# 24V_Power_Supply.net
KiCad netlist of a schematic drawn in Altium Designer
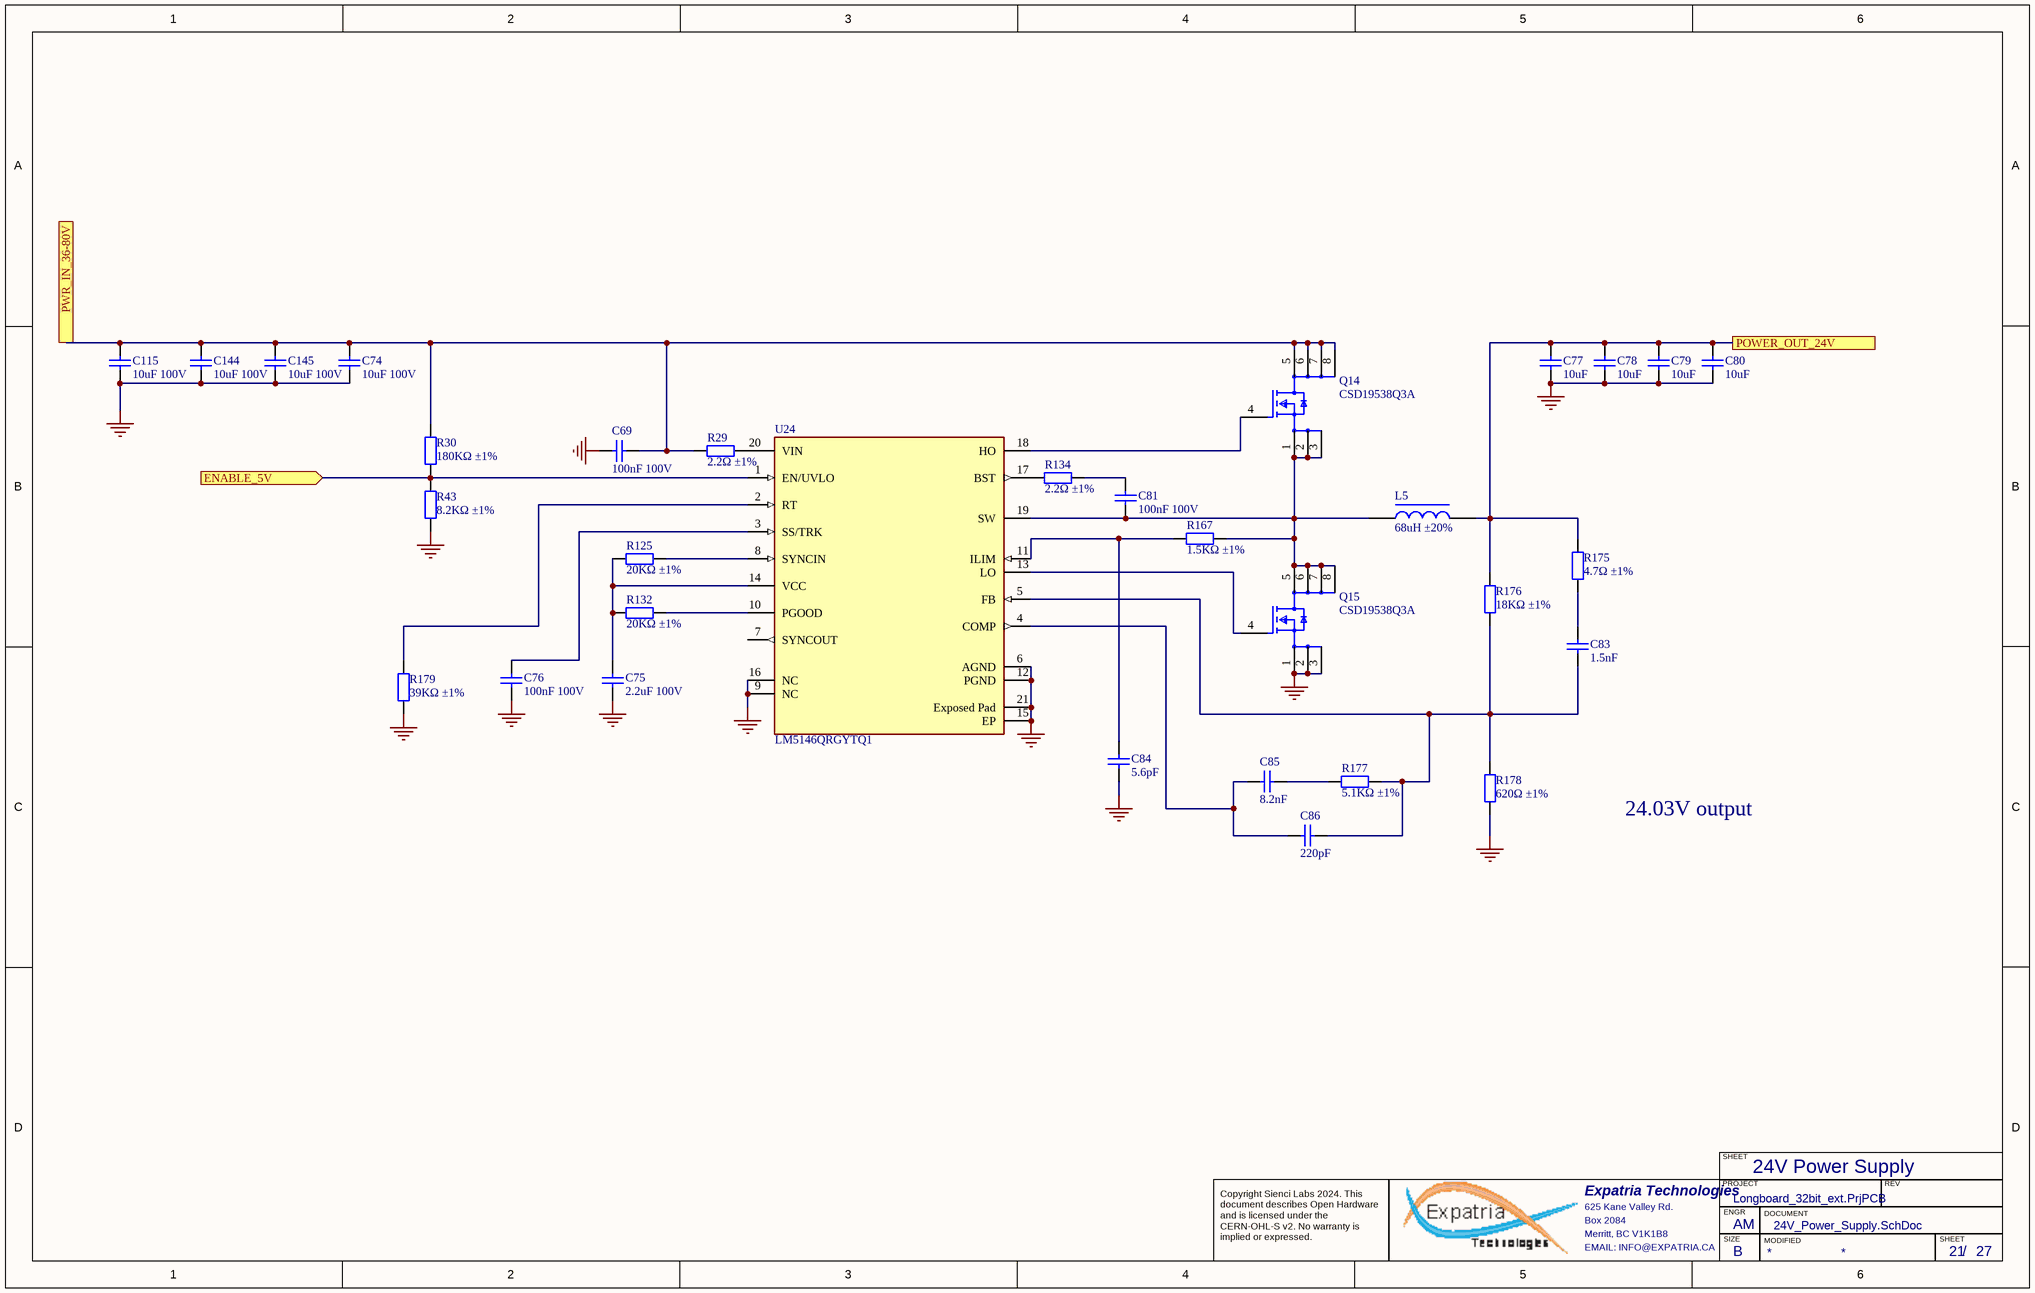
[diagram p0: 24V_Power_Supply.SchDoc]

(export (version "E")
  (design (tool "Eeschema 10.0.6"))
  (components
    (comp (ref "C69")
      (value "100nF 100V")
      (footprint "0805_C")
      (description "Chip capacitors")
      (fields
        (field (name "MANUFACTURER") "Guangdong Fenghua Advanced Tech")
        (field (name "MANUFACTURER PART NUMBER") "0805B104K101NT")
      )
      (libsource (lib "Cap") (part "0805 100nF (683) 10% 100V"))
    )
    (comp (ref "C74")
      (value "10uF 100V")
      (footprint "1210_C")
      (description "Chip capacitors")
      (fields (field (name "MANUFACTURER") "Murata") (field (name "TOLERANCE") "10%"))
      (libsource (lib "Sienci_Labs") (part "1210 10uF (106) 10% 100V"))
    )
    (comp (ref "C75")
      (value "2.2uF 100V")
      (footprint "1206_C")
      (description "Chip capacitors")
      (fields
        (field (name "MANUFACTURER") "Samsung Electro-Mechanics")
        (field (name "MANUFACTURER PART NUMBER") "CL31A225KBHNNNE")
      )
      (libsource (lib "Cap") (part "1206 2.2uF (225) 10% 50V"))
    )
    (comp (ref "C76")
      (value "100nF 100V")
      (footprint "0805_C")
      (description "Chip capacitors")
      (fields
        (field (name "MANUFACTURER") "Guangdong Fenghua Advanced Tech")
        (field (name "MANUFACTURER PART NUMBER") "0805B104K101NT")
      )
      (libsource (lib "Cap") (part "0805 100nF (683) 10% 100V"))
    )
    (comp (ref "C77")
      (value "10uF")
      (footprint "1206_C")
      (description "50V 10uF X5R ±10% 1206 Multilayer Ceramic Capacitors MLCC - SMD/SMT ROHS")
      (fields (field (name "MANUFACTURER") "Samsung Electro-Mechanics") (field (name "TOLERANCE") "10%"))
      (libsource (lib "Sienci_Labs") (part "1206 10uF (106) 10% 50V"))
    )
    (comp (ref "C78")
      (value "10uF")
      (footprint "1206_C")
      (description "50V 10uF X5R ±10% 1206 Multilayer Ceramic Capacitors MLCC - SMD/SMT ROHS")
      (fields (field (name "MANUFACTURER") "Samsung Electro-Mechanics") (field (name "TOLERANCE") "10%"))
      (libsource (lib "Sienci_Labs") (part "1206 10uF (106) 10% 50V"))
    )
    (comp (ref "C79")
      (value "10uF")
      (footprint "1206_C")
      (description "50V 10uF X5R ±10% 1206 Multilayer Ceramic Capacitors MLCC - SMD/SMT ROHS")
      (fields (field (name "MANUFACTURER") "Samsung Electro-Mechanics") (field (name "TOLERANCE") "10%"))
      (libsource (lib "Sienci_Labs") (part "1206 10uF (106) 10% 50V"))
    )
    (comp (ref "C80")
      (value "10uF")
      (footprint "1206_C")
      (description "50V 10uF X5R ±10% 1206 Multilayer Ceramic Capacitors MLCC - SMD/SMT ROHS")
      (fields (field (name "MANUFACTURER") "Samsung Electro-Mechanics") (field (name "TOLERANCE") "10%"))
      (libsource (lib "Sienci_Labs") (part "1206 10uF (106) 10% 50V"))
    )
    (comp (ref "C81")
      (value "100nF 100V")
      (footprint "0805_C")
      (description "Chip capacitors")
      (fields
        (field (name "MANUFACTURER") "Guangdong Fenghua Advanced Tech")
        (field (name "MANUFACTURER PART NUMBER") "0805B104K101NT")
      )
      (libsource (lib "Cap") (part "0805 100nF (683) 10% 100V"))
    )
    (comp (ref "C83")
      (value "1.5nF")
      (footprint "0603_C")
      (description "Chip capacitors")
      (fields
        (field (name "MANUFACTURER") "Guangdong Fenghua Advanced Tech")
        (field (name "MANUFACTURER PART NUMBER") "0603B152K500NT")
      )
      (libsource (lib "Cap") (part "0603 1.5nF (152) 10% 50V"))
    )
    (comp (ref "C84")
      (value "5.6pF")
      (footprint "0603_C")
      (description "Chip capacitors")
      (fields
        (field (name "MANUFACTURER") "Murata")
        (field (name "MANUFACTURER PART NUMBER") "GQM1875C2E5R6BB12D")
      )
      (libsource (lib "Cap") (part "0603 4.7pF (4R7) 0.25pF 50V"))
    )
    (comp (ref "C85")
      (value "8.2nF")
      (footprint "0603_C")
      (description "50V 8.2nF X7R ±10% 0603 Multilayer Ceramic Capacitors MLCC - SMD/SMT ROHS")
      (fields (field (name "MANUFACTURER") "YAGEO") (field (name "TOLERANCE") "10%"))
      (libsource (lib "Sienci_Labs") (part "0603 8.2nF (822) 10% 50V"))
    )
    (comp (ref "C86")
      (value "220pF")
      (footprint "0603_C")
      (description "Chip capacitors")
      (fields
        (field (name "MANUFACTURER") "Samsung Electro-Mechanics")
        (field (name "MANUFACTURER PART NUMBER") "CL10B221KB8NNNC")
      )
      (libsource (lib "Cap") (part "0603 220pF (221) 10% 50V"))
    )
    (comp (ref "C115")
      (value "10uF 100V")
      (footprint "1210_C")
      (description "Chip capacitors")
      (fields (field (name "MANUFACTURER") "Murata") (field (name "TOLERANCE") "10%"))
      (libsource (lib "Sienci_Labs") (part "1210 10uF (106) 10% 100V"))
    )
    (comp (ref "C144")
      (value "10uF 100V")
      (footprint "1210_C")
      (description "Chip capacitors")
      (fields (field (name "MANUFACTURER") "Murata") (field (name "TOLERANCE") "10%"))
      (libsource (lib "Sienci_Labs") (part "1210 10uF (106) 10% 100V"))
    )
    (comp (ref "C145")
      (value "10uF 100V")
      (footprint "1210_C")
      (description "Chip capacitors")
      (fields (field (name "MANUFACTURER") "Murata") (field (name "TOLERANCE") "10%"))
      (libsource (lib "Sienci_Labs") (part "1210 10uF (106) 10% 100V"))
    )
    (comp (ref "L5")
      (value "68uH ±20%")
      (footprint "INDP126126X68N")
      (description "3A 68uH ±20% 64.8mΩ SMD Inductors (SMD) ROHS")
      (fields
        (field (name "MANUFACTURER") "hanxia")
        (field (name "MANUFACTURER PART NUMBER") "HX CYH125-68UH")
      )
      (libsource (lib "IUD") (part "12.5x12.5x6.5 68uH 20% 3A"))
    )
    (comp (ref "Q14")
      (value "CSD19538Q3A")
      (footprint "Universal_breakout:FP-DNH0008A-MFG")
      (fields (field (name "MANUFACTURER") "Texas Instruments"))
      (libsource (lib "MOS") (part "CSD19538Q3A"))
    )
    (comp (ref "Q15")
      (value "CSD19538Q3A")
      (footprint "Universal_breakout:FP-DNH0008A-MFG")
      (fields (field (name "MANUFACTURER") "Texas Instruments"))
      (libsource (lib "MOS") (part "CSD19538Q3A"))
    )
    (comp (ref "R29")
      (value "2.2Ω ±1%")
      (footprint "0603_R")
      (description "Chip resistor")
      (fields
        (field (name "MANUFACTURER") "Uniroyal Elec")
        (field (name "MANUFACTURER PART NUMBER") "0603WAF220KT5E")
      )
      (libsource (lib "RES") (part "0603 2.2R (2R20) 1%"))
    )
    (comp (ref "R30")
      (value "180KΩ ±1%")
      (footprint "0603_R")
      (description "Chip resistor")
      (fields
        (field (name "MANUFACTURER") "Uniroyal Elec")
        (field (name "MANUFACTURER PART NUMBER") "0603WAF1803T5E")
      )
      (libsource (lib "RES") (part "0603 180K (1803) 1%"))
    )
    (comp (ref "R43")
      (value "8.2KΩ ±1%")
      (footprint "0603_R")
      (description "Chip resistor")
      (fields
        (field (name "MANUFACTURER") "Uniroyal Elec")
        (field (name "MANUFACTURER PART NUMBER") "0603WAF8201T5E")
      )
      (libsource (lib "RES") (part "0603 8.2K (8201) 1%"))
    )
    (comp (ref "R125")
      (value "20KΩ ±1%")
      (footprint "0603_R")
      (description "Chip resistor")
      (fields
        (field (name "MANUFACTURER") "Uniroyal Elec")
        (field (name "MANUFACTURER PART NUMBER") "0603WAF2002T5E")
      )
      (libsource (lib "RES") (part "0603 20K (2002) 1%"))
    )
    (comp (ref "R132")
      (value "20KΩ ±1%")
      (footprint "0603_R")
      (description "Chip resistor")
      (fields
        (field (name "MANUFACTURER") "Uniroyal Elec")
        (field (name "MANUFACTURER PART NUMBER") "0603WAF2002T5E")
      )
      (libsource (lib "RES") (part "0603 20K (2002) 1%"))
    )
    (comp (ref "R134")
      (value "2.2Ω ±1%")
      (footprint "0603_R")
      (description "Chip resistor")
      (fields
        (field (name "MANUFACTURER") "Uniroyal Elec")
        (field (name "MANUFACTURER PART NUMBER") "0603WAF220KT5E")
      )
      (libsource (lib "RES") (part "0603 2.2R (2R20) 1%"))
    )
    (comp (ref "R167")
      (value "1.5KΩ ±1%")
      (footprint "0603_R")
      (description "Chip resistor")
      (fields
        (field (name "MANUFACTURER") "Uniroyal Elec")
        (field (name "MANUFACTURER PART NUMBER") "0603WAF1501T5E")
      )
      (libsource (lib "RES") (part "0603 1.5K (1501) 1%"))
    )
    (comp (ref "R175")
      (value "4.7Ω ±1%")
      (footprint "0603_R")
      (description "Chip resistor")
      (fields
        (field (name "MANUFACTURER") "Uniroyal Elec")
        (field (name "MANUFACTURER PART NUMBER") "0603WAF470KT5E")
      )
      (libsource (lib "RES") (part "0603 4.7R (4R70) 1%"))
    )
    (comp (ref "R176")
      (value "18KΩ ±1%")
      (footprint "0603_R")
      (description "Chip resistor")
      (fields
        (field (name "MANUFACTURER") "Uniroyal Elec")
        (field (name "MANUFACTURER PART NUMBER") "0603WAF1802T5E")
      )
      (libsource (lib "RES") (part "0603 18K (1802) 1%"))
    )
    (comp (ref "R177")
      (value "5.1KΩ ±1%")
      (footprint "0603_R")
      (description "Chip resistor")
      (fields
        (field (name "MANUFACTURER") "Uniroyal Elec")
        (field (name "MANUFACTURER PART NUMBER") "0603WAF5101T5E")
      )
      (libsource (lib "RES") (part "0603 5.1K (5101) 1%"))
    )
    (comp (ref "R178")
      (value "620Ω ±1%")
      (footprint "0603_R")
      (description "Chip resistor")
      (fields
        (field (name "MANUFACTURER") "Uniroyal Elec")
        (field (name "MANUFACTURER PART NUMBER") "0603WAF6200T5E")
      )
      (libsource (lib "RES") (part "0603 620R (6200) 1%"))
    )
    (comp (ref "R179")
      (value "39KΩ ±1%")
      (footprint "0603_R")
      (description "Chip resistor")
      (fields
        (field (name "MANUFACTURER") "Uniroyal Elec")
        (field (name "MANUFACTURER PART NUMBER") "0603WAF3902T5E")
      )
      (libsource (lib "RES") (part "0603 39K (3902) 1%"))
    )
    (comp (ref "U24")
      (value "LM5146QRGYTQ1")
      (footprint "FP-RGY0020B-MFG")
      (description "Automotive 100-V synchronous buck DC/DC controller with wide duty-cycle range 20-VQFN -40 to 150")
      (fields (field (name "MANUFACTURER") "Texas Instruments"))
      (libsource (lib "Sienci_Labs") (part "LM5146QRGYTQ1"))
    )
  )
  (nets
    (net (code "1") (name "/ENABLE_5V") (class "Default")
      (node (ref "R30") (pin "1") (pinfunction "1_1") (pintype "passive"))
      (node (ref "R43") (pin "2") (pinfunction "2_2") (pintype "passive"))
      (node (ref "U24") (pin "1") (pinfunction "EN/UVLO_1") (pintype "input"))
    )
    (net (code "2") (name "/POWER_OUT_24V") (class "Default")
      (node (ref "C77") (pin "2") (pinfunction "2_2") (pintype "passive"))
      (node (ref "C78") (pin "2") (pinfunction "2_2") (pintype "passive"))
      (node (ref "C79") (pin "2") (pinfunction "2_2") (pintype "passive"))
      (node (ref "C80") (pin "2") (pinfunction "2_2") (pintype "passive"))
      (node (ref "L5") (pin "2") (pinfunction "2_2") (pintype "passive"))
      (node (ref "R175") (pin "1") (pinfunction "1_1") (pintype "passive"))
      (node (ref "R176") (pin "2") (pinfunction "2_2") (pintype "passive"))
    )
    (net (code "3") (name "/PWR_IN_36-80V") (class "Default")
      (node (ref "C115") (pin "2") (pinfunction "2_2") (pintype "passive"))
      (node (ref "C144") (pin "2") (pinfunction "2_2") (pintype "passive"))
      (node (ref "C145") (pin "2") (pinfunction "2_2") (pintype "passive"))
      (node (ref "C69") (pin "2") (pinfunction "2_2") (pintype "passive"))
      (node (ref "C74") (pin "2") (pinfunction "2_2") (pintype "passive"))
      (node (ref "Q14") (pin "5") (pinfunction "D_5") (pintype "passive"))
      (node (ref "Q14") (pin "6") (pinfunction "D_6") (pintype "passive"))
      (node (ref "Q14") (pin "7") (pinfunction "D_7") (pintype "passive"))
      (node (ref "Q14") (pin "8") (pinfunction "D_8") (pintype "passive"))
      (node (ref "R29") (pin "1") (pinfunction "1_1") (pintype "passive"))
      (node (ref "R30") (pin "2") (pinfunction "2_2") (pintype "passive"))
    )
    (net (code "4") (name "GND") (class "Default")
      (node (ref "C115") (pin "1") (pinfunction "1_1") (pintype "passive"))
      (node (ref "C144") (pin "1") (pinfunction "1_1") (pintype "passive"))
      (node (ref "C145") (pin "1") (pinfunction "1_1") (pintype "passive"))
      (node (ref "C69") (pin "1") (pinfunction "1_1") (pintype "passive"))
      (node (ref "C74") (pin "1") (pinfunction "1_1") (pintype "passive"))
      (node (ref "C75") (pin "1") (pinfunction "1_1") (pintype "passive"))
      (node (ref "C76") (pin "1") (pinfunction "1_1") (pintype "passive"))
      (node (ref "C77") (pin "1") (pinfunction "1_1") (pintype "passive"))
      (node (ref "C78") (pin "1") (pinfunction "1_1") (pintype "passive"))
      (node (ref "C79") (pin "1") (pinfunction "1_1") (pintype "passive"))
      (node (ref "C80") (pin "1") (pinfunction "1_1") (pintype "passive"))
      (node (ref "C84") (pin "1") (pinfunction "1_1") (pintype "passive"))
      (node (ref "Q15") (pin "1") (pinfunction "S_1") (pintype "passive"))
      (node (ref "Q15") (pin "2") (pinfunction "S_2") (pintype "passive"))
      (node (ref "Q15") (pin "3") (pinfunction "S_3") (pintype "passive"))
      (node (ref "R178") (pin "1") (pinfunction "1_1") (pintype "passive"))
      (node (ref "R179") (pin "1") (pinfunction "1_1") (pintype "passive"))
      (node (ref "R43") (pin "1") (pinfunction "1_1") (pintype "passive"))
      (node (ref "U24") (pin "12") (pinfunction "PGND_12") (pintype "power_in"))
      (node (ref "U24") (pin "15") (pinfunction "EP_15") (pintype "power_in"))
      (node (ref "U24") (pin "16") (pinfunction "NC_16") (pintype "passive"))
      (node (ref "U24") (pin "21") (pinfunction "Exposed_Pad_21") (pintype "power_in"))
      (node (ref "U24") (pin "6") (pinfunction "AGND_6") (pintype "power_in"))
      (node (ref "U24") (pin "9") (pinfunction "NC_9") (pintype "passive"))
    )
    (net (code "5") (name "Net-(C81-Pad2)") (class "Default")
      (node (ref "C81") (pin "2") (pinfunction "2_2") (pintype "passive"))
      (node (ref "R134") (pin "2") (pinfunction "2_2") (pintype "passive"))
    )
    (net (code "6") (name "Net-(C83-Pad2)") (class "Default")
      (node (ref "C83") (pin "2") (pinfunction "2_2") (pintype "passive"))
      (node (ref "R175") (pin "2") (pinfunction "2_2") (pintype "passive"))
    )
    (net (code "7") (name "Net-(C85-Pad2)") (class "Default")
      (node (ref "C85") (pin "2") (pinfunction "2_2") (pintype "passive"))
      (node (ref "R177") (pin "1") (pinfunction "1_1") (pintype "passive"))
    )
    (net (code "8") (name "Net-(Q14-G)") (class "Default")
      (node (ref "Q14") (pin "4") (pinfunction "G_4") (pintype "passive"))
      (node (ref "U24") (pin "18") (pinfunction "HO_18") (pintype "power_in"))
    )
    (net (code "9") (name "Net-(Q15-G)") (class "Default")
      (node (ref "Q15") (pin "4") (pinfunction "G_4") (pintype "passive"))
      (node (ref "U24") (pin "13") (pinfunction "LO_13") (pintype "power_in"))
    )
    (net (code "10") (name "Net-(U24-BST)") (class "Default")
      (node (ref "R134") (pin "1") (pinfunction "1_1") (pintype "passive"))
      (node (ref "U24") (pin "17") (pinfunction "BST_17") (pintype "output"))
    )
    (net (code "11") (name "Net-(U24-COMP)") (class "Default")
      (node (ref "C85") (pin "1") (pinfunction "1_1") (pintype "passive"))
      (node (ref "C86") (pin "1") (pinfunction "1_1") (pintype "passive"))
      (node (ref "U24") (pin "4") (pinfunction "COMP_4") (pintype "output"))
    )
    (net (code "12") (name "Net-(U24-FB)") (class "Default")
      (node (ref "C83") (pin "1") (pinfunction "1_1") (pintype "passive"))
      (node (ref "C86") (pin "2") (pinfunction "2_2") (pintype "passive"))
      (node (ref "R176") (pin "1") (pinfunction "1_1") (pintype "passive"))
      (node (ref "R177") (pin "2") (pinfunction "2_2") (pintype "passive"))
      (node (ref "R178") (pin "2") (pinfunction "2_2") (pintype "passive"))
      (node (ref "U24") (pin "5") (pinfunction "FB_5") (pintype "input"))
    )
    (net (code "13") (name "Net-(U24-ILIM)") (class "Default")
      (node (ref "C84") (pin "2") (pinfunction "2_2") (pintype "passive"))
      (node (ref "R167") (pin "1") (pinfunction "1_1") (pintype "passive"))
      (node (ref "U24") (pin "11") (pinfunction "ILIM_11") (pintype "input"))
    )
    (net (code "14") (name "Net-(U24-PGOOD)") (class "Default")
      (node (ref "R132") (pin "2") (pinfunction "2_2") (pintype "passive"))
      (node (ref "U24") (pin "10") (pinfunction "PGOOD_10") (pintype "open_collector"))
    )
    (net (code "15") (name "Net-(U24-RT)") (class "Default")
      (node (ref "R179") (pin "2") (pinfunction "2_2") (pintype "passive"))
      (node (ref "U24") (pin "2") (pinfunction "RT_2") (pintype "input"))
    )
    (net (code "16") (name "Net-(U24-SS{slash}TRK)") (class "Default")
      (node (ref "C76") (pin "2") (pinfunction "2_2") (pintype "passive"))
      (node (ref "U24") (pin "3") (pinfunction "SS/TRK_3") (pintype "input"))
    )
    (net (code "17") (name "Net-(U24-SW)") (class "Default")
      (node (ref "C81") (pin "1") (pinfunction "1_1") (pintype "passive"))
      (node (ref "L5") (pin "1") (pinfunction "1_1") (pintype "passive"))
      (node (ref "Q14") (pin "1") (pinfunction "S_1") (pintype "passive"))
      (node (ref "Q14") (pin "2") (pinfunction "S_2") (pintype "passive"))
      (node (ref "Q14") (pin "3") (pinfunction "S_3") (pintype "passive"))
      (node (ref "Q15") (pin "5") (pinfunction "D_5") (pintype "passive"))
      (node (ref "Q15") (pin "6") (pinfunction "D_6") (pintype "passive"))
      (node (ref "Q15") (pin "7") (pinfunction "D_7") (pintype "passive"))
      (node (ref "Q15") (pin "8") (pinfunction "D_8") (pintype "passive"))
      (node (ref "R167") (pin "2") (pinfunction "2_2") (pintype "passive"))
      (node (ref "U24") (pin "19") (pinfunction "SW_19") (pintype "power_in"))
    )
    (net (code "18") (name "Net-(U24-SYNCIN)") (class "Default")
      (node (ref "R125") (pin "2") (pinfunction "2_2") (pintype "passive"))
      (node (ref "U24") (pin "8") (pinfunction "SYNCIN_8") (pintype "input"))
    )
    (net (code "19") (name "Net-(U24-VCC)") (class "Default")
      (node (ref "C75") (pin "2") (pinfunction "2_2") (pintype "passive"))
      (node (ref "R125") (pin "1") (pinfunction "1_1") (pintype "passive"))
      (node (ref "R132") (pin "1") (pinfunction "1_1") (pintype "passive"))
      (node (ref "U24") (pin "14") (pinfunction "VCC_14") (pintype "power_in"))
    )
    (net (code "20") (name "Net-(U24-VIN)") (class "Default")
      (node (ref "R29") (pin "2") (pinfunction "2_2") (pintype "passive"))
      (node (ref "U24") (pin "20") (pinfunction "VIN_20") (pintype "power_in"))
    )
    (net (code "21") (name "unconnected-(U24-SYNCOUT-Pad7)") (class "Default")
      (node (ref "U24") (pin "7") (pinfunction "SYNCOUT_7") (pintype "output"))
    )
  )
)
